# TriMod_Adapter_2.net
KiCad netlist of a schematic drawn in Altium Designer
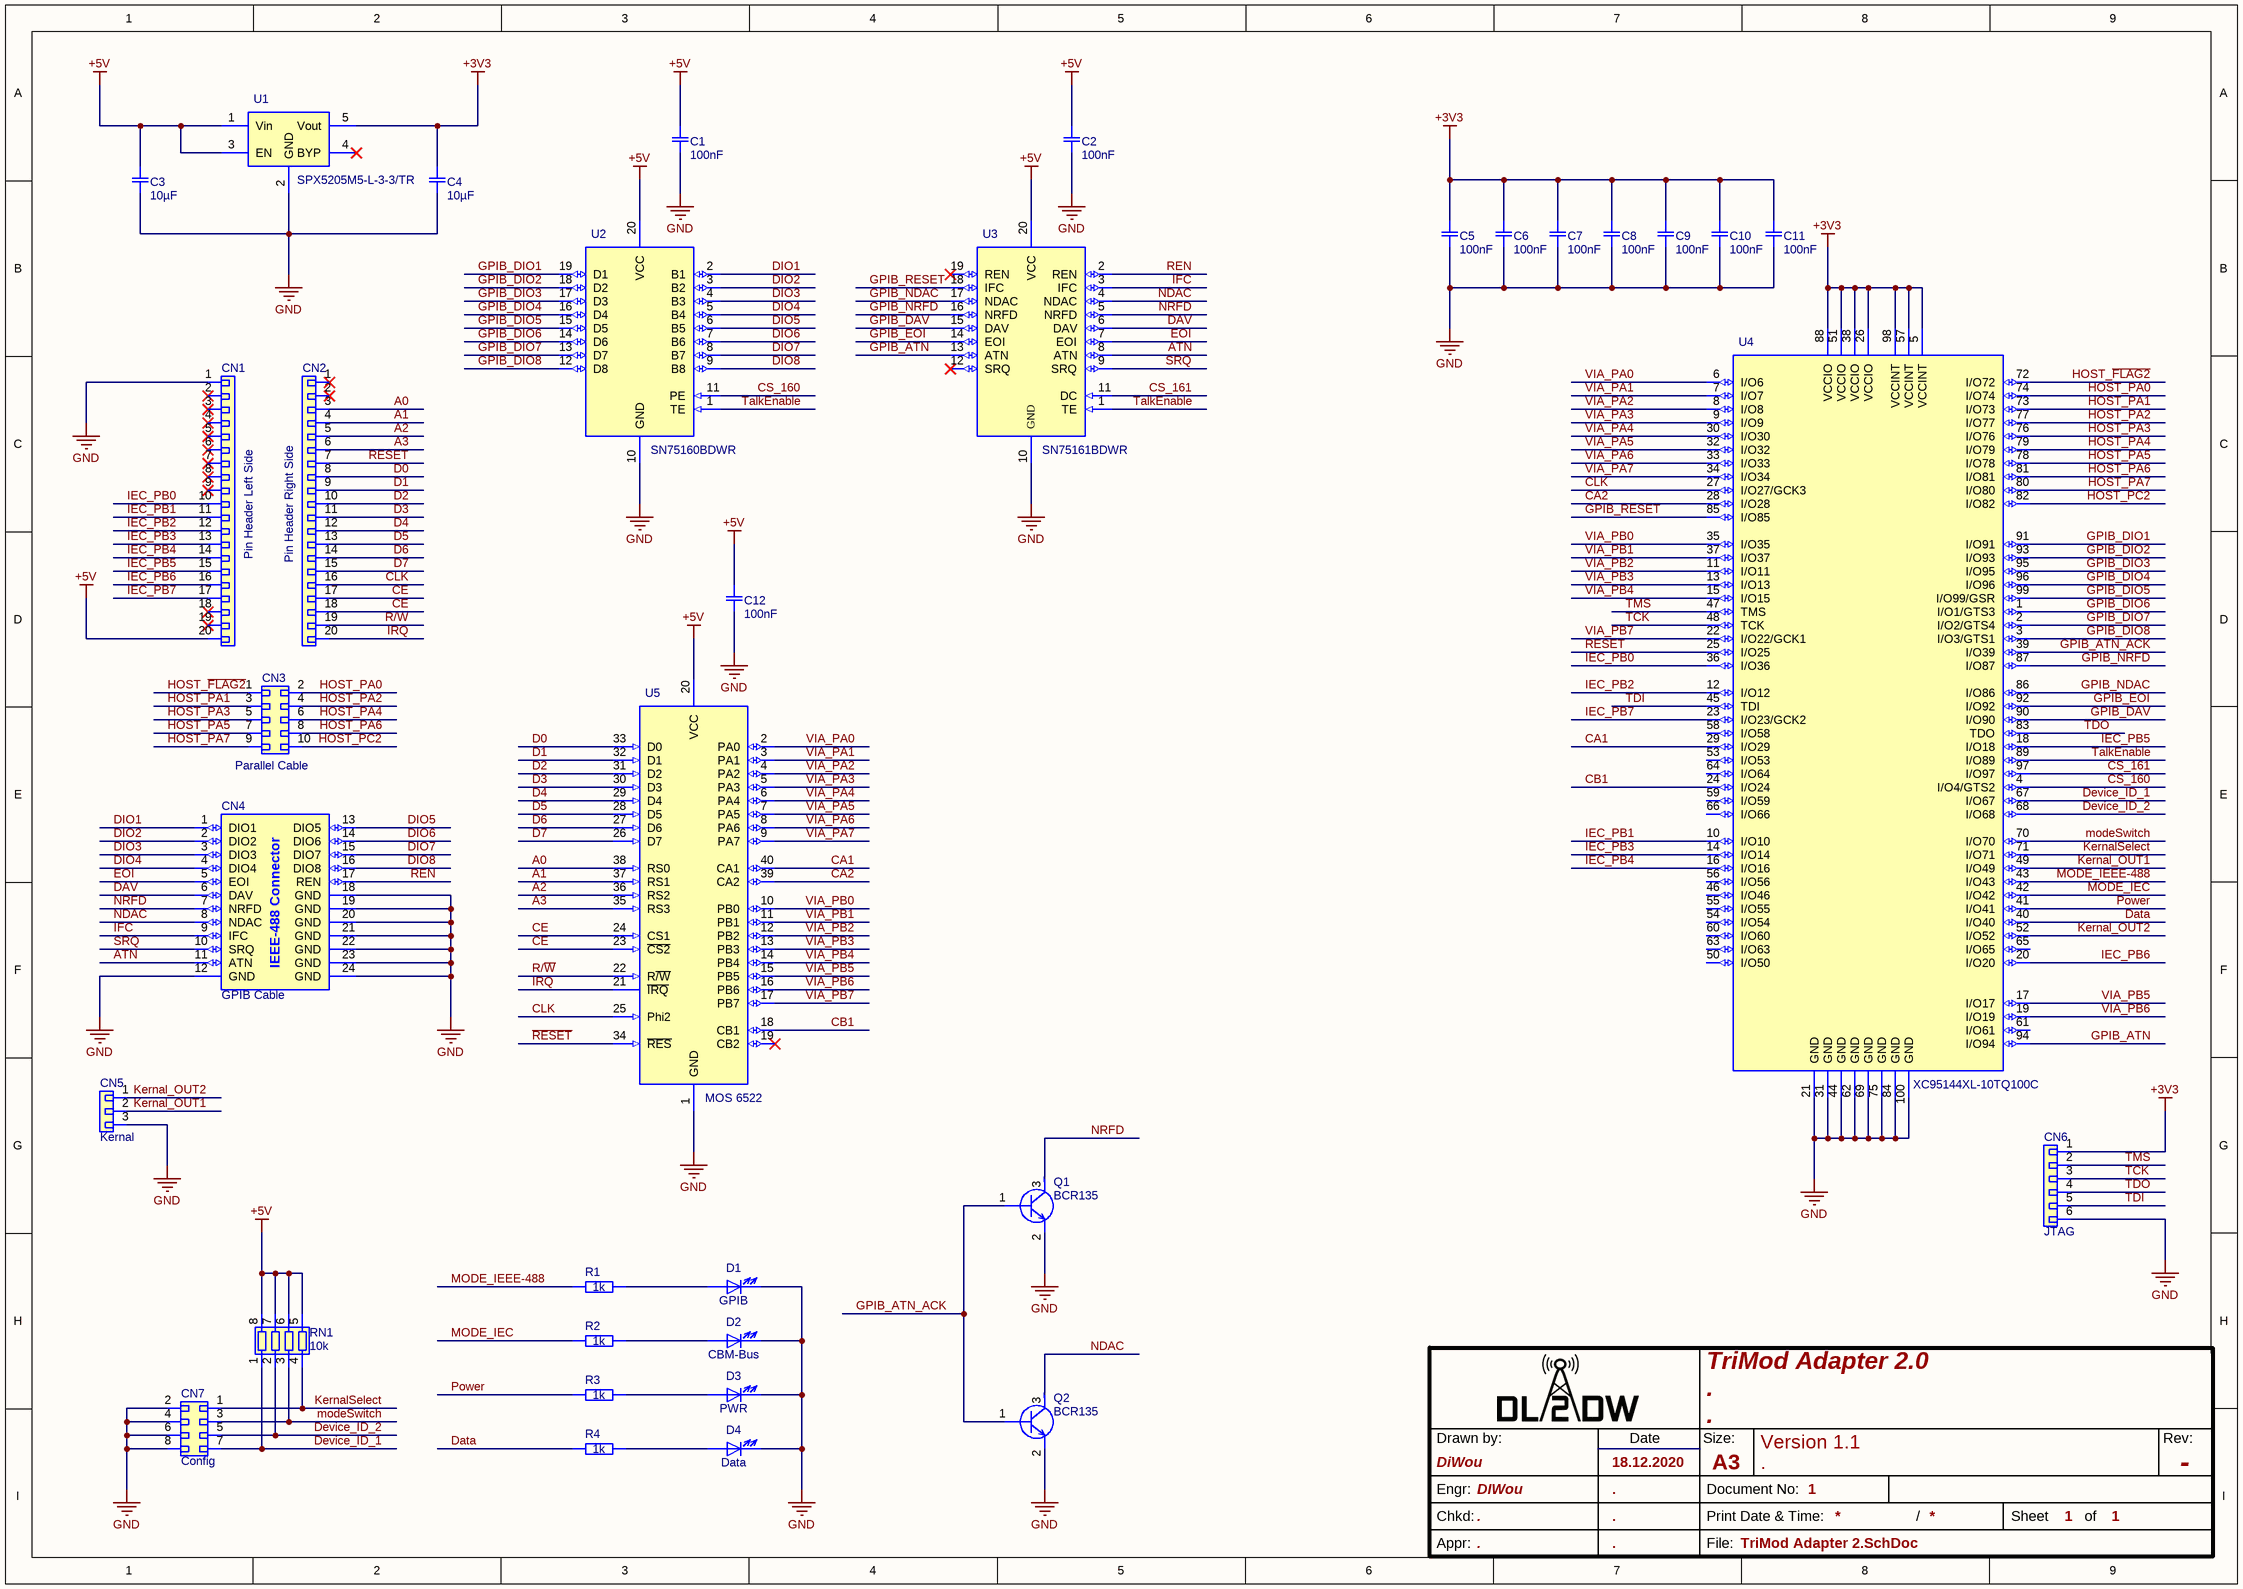
[diagram p0: TriMod Adapter 2.SchDoc]

(export (version "E")
  (design (tool "Eeschema 10.0.6"))
  (components
    (comp (ref "C1")
      (value "100nF")
      (footprint "CAP 100nF SMD 0603 C0603C104J3RACTU")
      (fields (field (name "TOLERANCE") "5%") (field (name "VOLTAGE") "25V"))
      (libsource (lib "PCB-Tech Cloud") (part "Capacitor"))
    )
    (comp (ref "C2")
      (value "100nF")
      (footprint "CAP 100nF SMD 0603 C0603C104J3RACTU")
      (fields (field (name "TOLERANCE") "5%") (field (name "VOLTAGE") "25V"))
      (libsource (lib "PCB-Tech Cloud") (part "Capacitor"))
    )
    (comp (ref "C3")
      (value "10µF")
      (footprint "Kemet C0805CxxxK8RACTU Series H=1.4mm")
      (description "KEMET - C0805C106K8RACTU - CAP, 10µF, 10V, 10%, X7R, 0805")
      (fields (field (name "VOLTAGE") "10V") (field (name "TOLERANCE") "10%"))
      (libsource (lib "PCB-Tech Cloud") (part "Capacitor"))
    )
    (comp (ref "C4")
      (value "10µF")
      (footprint "Kemet C0805CxxxK8RACTU Series H=1.4mm")
      (description "KEMET - C0805C106K8RACTU - CAP, 10µF, 10V, 10%, X7R, 0805")
      (fields (field (name "VOLTAGE") "10V") (field (name "TOLERANCE") "10%"))
      (libsource (lib "PCB-Tech Cloud") (part "Capacitor"))
    )
    (comp (ref "C5")
      (value "100nF")
      (footprint "CAP 100nF SMD 0603 C0603C104J3RACTU")
      (fields (field (name "TOLERANCE") "5%") (field (name "VOLTAGE") "25V"))
      (libsource (lib "PCB-Tech Cloud") (part "Capacitor"))
    )
    (comp (ref "C6")
      (value "100nF")
      (footprint "CAP 100nF SMD 0603 C0603C104J3RACTU")
      (fields (field (name "TOLERANCE") "5%") (field (name "VOLTAGE") "25V"))
      (libsource (lib "PCB-Tech Cloud") (part "Capacitor"))
    )
    (comp (ref "C7")
      (value "100nF")
      (footprint "CAP 100nF SMD 0603 C0603C104J3RACTU")
      (fields (field (name "TOLERANCE") "5%") (field (name "VOLTAGE") "25V"))
      (libsource (lib "PCB-Tech Cloud") (part "Capacitor"))
    )
    (comp (ref "C8")
      (value "100nF")
      (footprint "CAP 100nF SMD 0603 C0603C104J3RACTU")
      (fields (field (name "TOLERANCE") "5%") (field (name "VOLTAGE") "25V"))
      (libsource (lib "PCB-Tech Cloud") (part "Capacitor"))
    )
    (comp (ref "C9")
      (value "100nF")
      (footprint "CAP 100nF SMD 0603 C0603C104J3RACTU")
      (fields (field (name "TOLERANCE") "5%") (field (name "VOLTAGE") "25V"))
      (libsource (lib "PCB-Tech Cloud") (part "Capacitor"))
    )
    (comp (ref "C10")
      (value "100nF")
      (footprint "CAP 100nF SMD 0603 C0603C104J3RACTU")
      (fields (field (name "TOLERANCE") "5%") (field (name "VOLTAGE") "25V"))
      (libsource (lib "PCB-Tech Cloud") (part "Capacitor"))
    )
    (comp (ref "C11")
      (value "100nF")
      (footprint "CAP 100nF SMD 0603 C0603C104J3RACTU")
      (fields (field (name "TOLERANCE") "5%") (field (name "VOLTAGE") "25V"))
      (libsource (lib "PCB-Tech Cloud") (part "Capacitor"))
    )
    (comp (ref "C12")
      (value "100nF")
      (footprint "CAP 100nF SMD 0603 C0603C104J3RACTU")
      (fields (field (name "TOLERANCE") "5%") (field (name "VOLTAGE") "25V"))
      (libsource (lib "PCB-Tech Cloud") (part "Capacitor"))
    )
    (comp (ref "CN1")
      (value "Pin Header Left Side")
      (footprint "Pin Header 01x20 2.54mm precision Horizontal Male")
      (description "Conn Header Vert 20POS 2MM")
      (libsource (lib "") (part "CONN 01x20_1"))
    )
    (comp (ref "CN2")
      (value "Pin Header Right Side")
      (footprint "Pin Header 01x20 2.54mm precision Horizontal Male")
      (description "Conn Header Vert 20POS 2MM")
      (libsource (lib "PCB-Tech Cloud") (part "CONN 01x20"))
    )
    (comp (ref "CN3")
      (value "Parallel Cable")
      (footprint "MPE 369-1-010 Buchsenleisten MicroMatch 1,27 mm,2X05,gerade")
      (description "Grid pitch: 1.27 mm BL2/15-0400GTT-010 RU MPE Garry Conten")
      (libsource (lib "PCB-Tech Cloud") (part "CONN 02x05 Odd Even mirrored"))
    )
    (comp (ref "CN4")
      (value "GPIB Cable")
      (footprint "IEEE-488 Micro Match Connector")
      (description "IEEE-488 IDC Connector Right Angle or Straight")
      (libsource (lib "PCB-Tech Cloud") (part "IEEE-488 Connector"))
    )
    (comp (ref "CN5")
      (value "Kernal")
      (footprint "Pin Header 01x03 2.54mm Horizontal Male")
      (description "CONN HEADER .100\" SNGL STR 3POS")
      (libsource (lib "PCB-Tech Cloud") (part "CONN 01x03"))
    )
    (comp (ref "CN6")
      (value "JTAG")
      (footprint "Pin Header 01x06 2.54mm Horizontal Male")
      (description "CONN HEADER VERT 6POS 2.54MM")
      (libsource (lib "PCB-Tech Cloud") (part "CONN 01x06"))
    )
    (comp (ref "CN7")
      (value "Config")
      (footprint "Pin Header 02x04 2.54mm Horizontal Male")
      (description "CONN HEADER .100\" DUAL STR 8POS")
      (libsource (lib "PCB-Tech Cloud") (part "CONN 02x04 Odd Even"))
    )
    (comp (ref "D1")
      (value "GPIB")
      (footprint "LED Blue SMD 0603")
      (description "LED BLUE DIFFUSED 0603 SMD")
      (libsource (lib "PCB-Tech Cloud") (part "LED Standard"))
    )
    (comp (ref "D2")
      (value "CBM-Bus")
      (footprint "LED Green SMD 0603")
      (description "LED BLUE DIFFUSED 0603 SMD")
      (libsource (lib "PCB-Tech Cloud") (part "LED Standard"))
    )
    (comp (ref "D3")
      (value "PWR")
      (footprint "LED Red SMD 0603")
      (description "LED RED DIFFUSED 0603 SMD")
      (libsource (lib "PCB-Tech Cloud") (part "LED Standard"))
    )
    (comp (ref "D4")
      (value "Data")
      (footprint "LED Yellow SMD 0603")
      (description "LED YELLOW DIFFUSED 0603 SMD")
      (libsource (lib "PCB-Tech Cloud") (part "LED Standard"))
    )
    (comp (ref "Q1")
      (value "BCR135")
      (footprint "BCR135 SOT23")
      (description "BCR135 Series NPN 50 V 100 mA SMT Silicon Digital Transistor - SOT-23-3")
      (libsource (lib "PCB-Tech Cloud") (part "Transistor NPN BEC"))
    )
    (comp (ref "Q2")
      (value "BCR135")
      (footprint "BCR135 SOT23")
      (description "BCR135 Series NPN 50 V 100 mA SMT Silicon Digital Transistor - SOT-23-3")
      (libsource (lib "PCB-Tech Cloud") (part "Transistor NPN BEC"))
    )
    (comp (ref "R1")
      (value "1k")
      (footprint "1k Ohm R 0603 SMD")
      (description "RES SMD 1K OHM 1% 1/10W 0603")
      (fields (field (name "TOLERANCE") "1%"))
      (libsource (lib "PCB-Tech Cloud") (part "Resistor"))
    )
    (comp (ref "R2")
      (value "1k")
      (footprint "1k Ohm R 0603 SMD")
      (description "RES SMD 1K OHM 1% 1/10W 0603")
      (fields (field (name "TOLERANCE") "1%"))
      (libsource (lib "PCB-Tech Cloud") (part "Resistor"))
    )
    (comp (ref "R3")
      (value "1k")
      (footprint "1k Ohm R 0603 SMD")
      (description "RES SMD 1K OHM 1% 1/10W 0603")
      (fields (field (name "TOLERANCE") "1%"))
      (libsource (lib "PCB-Tech Cloud") (part "Resistor"))
    )
    (comp (ref "R4")
      (value "1k")
      (footprint "1k Ohm R 0603 SMD")
      (description "RES SMD 1K OHM 1% 1/10W 0603")
      (fields (field (name "TOLERANCE") "1%"))
      (libsource (lib "PCB-Tech Cloud") (part "Resistor"))
    )
    (comp (ref "RN1")
      (value "10k")
      (footprint "RES ARRAY 4 RES 10K OHM 0804")
      (description "RES ARRAY 4 RES 10K OHM 0804")
      (fields (field (name "TOLERANCE") "1%"))
      (libsource (lib "PCB-Tech Cloud") (part "Resistor Pack x4"))
    )
    (comp (ref "U1")
      (value "SPX5205M5-L-3-3/TR")
      (footprint "SOT-23-5")
      (description "LDO Regulator Pos 3.3V 0.15A 5-Pin SOT-23 T/R")
      (libsource (lib "PCB-Tech Cloud") (part "SPX5205M5-L-3-3/TR"))
    )
    (comp (ref "U2")
      (value "SN75160BDWR")
      (footprint "SN75160BDWR SOIC-20 W7.5mm P1,27mm")
      (description "TEXAS INSTRUMENTS         SN75160BDWR.            GENERAL-PURPOSE INTERFACE BUS  ((NW))")
      (libsource (lib "PCB-Tech Cloud") (part "SN75160B"))
    )
    (comp (ref "U3")
      (value "SN75161BDWR")
      (footprint "SN75161BDWR SOIC-20 W7.5mm P1,27mm")
      (description "TEXAS INSTRUMENTS         SN75161BDWR")
      (libsource (lib "PCB-Tech Cloud") (part "SN75161B"))
    )
    (comp (ref "U4")
      (value "XC95144XL-10TQ100C")
      (footprint "TQFP-100 P0.5mm XC95144XL-7TQ100C")
      (description "IC CPLD 144MC 7.5NS 100TQFP")
      (libsource (lib "PCB-Tech Cloud") (part "XC95144XL-TQG100C"))
    )
    (comp (ref "U5")
      (value "MOS 6522")
      (footprint "MOS 6522 with Socket")
      (description "I/O Controller Interface IC Versatile Interface Adapter")
      (libsource (lib "PCB-Tech Cloud") (part "MOS 6522"))
    )
  )
  (nets
    (net (code "1") (name "+3V3") (class "Default")
      (node (ref "C10") (pin "2") (pinfunction "2_2") (pintype "passive"))
      (node (ref "C11") (pin "2") (pinfunction "2_2") (pintype "passive"))
      (node (ref "C4") (pin "2") (pinfunction "2_2") (pintype "passive"))
      (node (ref "C5") (pin "2") (pinfunction "2_2") (pintype "passive"))
      (node (ref "C6") (pin "2") (pinfunction "2_2") (pintype "passive"))
      (node (ref "C7") (pin "2") (pinfunction "2_2") (pintype "passive"))
      (node (ref "C8") (pin "2") (pinfunction "2_2") (pintype "passive"))
      (node (ref "C9") (pin "2") (pinfunction "2_2") (pintype "passive"))
      (node (ref "CN6") (pin "1") (pinfunction "1_1") (pintype "passive"))
      (node (ref "U1") (pin "5") (pinfunction "Vout_5") (pintype "power_in"))
      (node (ref "U4") (pin "26") (pinfunction "VCCIO_26") (pintype "power_in"))
      (node (ref "U4") (pin "38") (pinfunction "VCCIO_38") (pintype "power_in"))
      (node (ref "U4") (pin "5") (pinfunction "VCCINT_5") (pintype "power_in"))
      (node (ref "U4") (pin "51") (pinfunction "VCCIO_51") (pintype "power_in"))
      (node (ref "U4") (pin "57") (pinfunction "VCCINT_57") (pintype "power_in"))
      (node (ref "U4") (pin "88") (pinfunction "VCCIO_88") (pintype "power_in"))
      (node (ref "U4") (pin "98") (pinfunction "VCCINT_98") (pintype "power_in"))
    )
    (net (code "2") (name "+5V") (class "Default")
      (node (ref "C1") (pin "2") (pinfunction "2_2") (pintype "passive"))
      (node (ref "C12") (pin "2") (pinfunction "2_2") (pintype "passive"))
      (node (ref "C2") (pin "2") (pinfunction "2_2") (pintype "passive"))
      (node (ref "C3") (pin "2") (pinfunction "2_2") (pintype "passive"))
      (node (ref "CN1") (pin "20") (pinfunction "20_20") (pintype "passive"))
      (node (ref "RN1") (pin "5") (pinfunction "5_5") (pintype "passive"))
      (node (ref "RN1") (pin "6") (pinfunction "6_6") (pintype "passive"))
      (node (ref "RN1") (pin "7") (pinfunction "7_7") (pintype "passive"))
      (node (ref "RN1") (pin "8") (pinfunction "8_8") (pintype "passive"))
      (node (ref "U1") (pin "1") (pinfunction "Vin_1") (pintype "power_in"))
      (node (ref "U1") (pin "3") (pinfunction "EN_3") (pintype "passive"))
      (node (ref "U2") (pin "20") (pinfunction "VCC_20") (pintype "power_in"))
      (node (ref "U3") (pin "20") (pinfunction "VCC_20") (pintype "power_in"))
      (node (ref "U5") (pin "20") (pinfunction "VCC_20") (pintype "power_in"))
    )
    (net (code "3") (name "/A0") (class "Default")
      (node (ref "CN2") (pin "3") (pinfunction "3_3") (pintype "passive"))
      (node (ref "U5") (pin "38") (pinfunction "RS0_38") (pintype "input"))
    )
    (net (code "4") (name "/A1") (class "Default")
      (node (ref "CN2") (pin "4") (pinfunction "4_4") (pintype "passive"))
      (node (ref "U5") (pin "37") (pinfunction "RS1_37") (pintype "input"))
    )
    (net (code "5") (name "/A2") (class "Default")
      (node (ref "CN2") (pin "5") (pinfunction "5_5") (pintype "passive"))
      (node (ref "U5") (pin "36") (pinfunction "RS2_36") (pintype "input"))
    )
    (net (code "6") (name "/A3") (class "Default")
      (node (ref "CN2") (pin "6") (pinfunction "6_6") (pintype "passive"))
      (node (ref "U5") (pin "35") (pinfunction "RS3_35") (pintype "input"))
    )
    (net (code "7") (name "/ATN") (class "Default")
      (node (ref "CN4") (pin "11") (pinfunction "ATN_11") (pintype "bidirectional"))
      (node (ref "U3") (pin "8") (pinfunction "ATN_8") (pintype "bidirectional"))
    )
    (net (code "8") (name "/CA1") (class "Default")
      (node (ref "U4") (pin "29") (pinfunction "I/O29_29") (pintype "bidirectional"))
      (node (ref "U5") (pin "40") (pinfunction "CA1_40") (pintype "bidirectional"))
    )
    (net (code "9") (name "/CA2") (class "Default")
      (node (ref "U4") (pin "28") (pinfunction "I/O28_28") (pintype "bidirectional"))
      (node (ref "U5") (pin "39") (pinfunction "CA2_39") (pintype "bidirectional"))
    )
    (net (code "10") (name "/CB1") (class "Default")
      (node (ref "U4") (pin "24") (pinfunction "I/O24_24") (pintype "bidirectional"))
      (node (ref "U5") (pin "18") (pinfunction "CB1_18") (pintype "bidirectional"))
    )
    (net (code "11") (name "/CE") (class "Default")
      (node (ref "CN2") (pin "17") (pinfunction "17_17") (pintype "passive"))
      (node (ref "U5") (pin "24") (pinfunction "CS1_24") (pintype "input"))
    )
    (net (code "12") (name "/CLK") (class "Default")
      (node (ref "CN2") (pin "16") (pinfunction "16_16") (pintype "passive"))
      (node (ref "U4") (pin "27") (pinfunction "I/O27/GCK3_27") (pintype "bidirectional"))
      (node (ref "U5") (pin "25") (pinfunction "Phi2_25") (pintype "input"))
    )
    (net (code "13") (name "/CS_160") (class "Default")
      (node (ref "U2") (pin "11") (pinfunction "PE_11") (pintype "input"))
      (node (ref "U4") (pin "4") (pinfunction "I/O4/GTS2_4") (pintype "bidirectional"))
    )
    (net (code "14") (name "/CS_161") (class "Default")
      (node (ref "U3") (pin "11") (pinfunction "DC_11") (pintype "input"))
      (node (ref "U4") (pin "97") (pinfunction "I/O97_97") (pintype "bidirectional"))
    )
    (net (code "15") (name "/D0") (class "Default")
      (node (ref "CN2") (pin "8") (pinfunction "8_8") (pintype "passive"))
      (node (ref "U5") (pin "33") (pinfunction "D0_33") (pintype "input"))
    )
    (net (code "16") (name "/D1") (class "Default")
      (node (ref "CN2") (pin "9") (pinfunction "9_9") (pintype "passive"))
      (node (ref "U5") (pin "32") (pinfunction "D1_32") (pintype "input"))
    )
    (net (code "17") (name "/D2") (class "Default")
      (node (ref "CN2") (pin "10") (pinfunction "10_10") (pintype "passive"))
      (node (ref "U5") (pin "31") (pinfunction "D2_31") (pintype "input"))
    )
    (net (code "18") (name "/D3") (class "Default")
      (node (ref "CN2") (pin "11") (pinfunction "11_11") (pintype "passive"))
      (node (ref "U5") (pin "30") (pinfunction "D3_30") (pintype "input"))
    )
    (net (code "19") (name "/D4") (class "Default")
      (node (ref "CN2") (pin "12") (pinfunction "12_12") (pintype "passive"))
      (node (ref "U5") (pin "29") (pinfunction "D4_29") (pintype "input"))
    )
    (net (code "20") (name "/D5") (class "Default")
      (node (ref "CN2") (pin "13") (pinfunction "13_13") (pintype "passive"))
      (node (ref "U5") (pin "28") (pinfunction "D5_28") (pintype "input"))
    )
    (net (code "21") (name "/D6") (class "Default")
      (node (ref "CN2") (pin "14") (pinfunction "14_14") (pintype "passive"))
      (node (ref "U5") (pin "27") (pinfunction "D6_27") (pintype "input"))
    )
    (net (code "22") (name "/D7") (class "Default")
      (node (ref "CN2") (pin "15") (pinfunction "15_15") (pintype "passive"))
      (node (ref "U5") (pin "26") (pinfunction "D7_26") (pintype "input"))
    )
    (net (code "23") (name "/DAV") (class "Default")
      (node (ref "CN4") (pin "6") (pinfunction "DAV_6") (pintype "bidirectional"))
      (node (ref "U3") (pin "6") (pinfunction "DAV_6") (pintype "bidirectional"))
    )
    (net (code "24") (name "/DIO1") (class "Default")
      (node (ref "CN4") (pin "1") (pinfunction "DIO1_1") (pintype "bidirectional"))
      (node (ref "U2") (pin "2") (pinfunction "B1_2") (pintype "bidirectional"))
    )
    (net (code "25") (name "/DIO2") (class "Default")
      (node (ref "CN4") (pin "2") (pinfunction "DIO2_2") (pintype "bidirectional"))
      (node (ref "U2") (pin "3") (pinfunction "B2_3") (pintype "bidirectional"))
    )
    (net (code "26") (name "/DIO3") (class "Default")
      (node (ref "CN4") (pin "3") (pinfunction "DIO3_3") (pintype "bidirectional"))
      (node (ref "U2") (pin "4") (pinfunction "B3_4") (pintype "bidirectional"))
    )
    (net (code "27") (name "/DIO4") (class "Default")
      (node (ref "CN4") (pin "4") (pinfunction "DIO4_4") (pintype "bidirectional"))
      (node (ref "U2") (pin "5") (pinfunction "B4_5") (pintype "bidirectional"))
    )
    (net (code "28") (name "/DIO5") (class "Default")
      (node (ref "CN4") (pin "13") (pinfunction "DIO5_13") (pintype "bidirectional"))
      (node (ref "U2") (pin "6") (pinfunction "B5_6") (pintype "bidirectional"))
    )
    (net (code "29") (name "/DIO6") (class "Default")
      (node (ref "CN4") (pin "14") (pinfunction "DIO6_14") (pintype "bidirectional"))
      (node (ref "U2") (pin "7") (pinfunction "B6_7") (pintype "bidirectional"))
    )
    (net (code "30") (name "/DIO7") (class "Default")
      (node (ref "CN4") (pin "15") (pinfunction "DIO7_15") (pintype "bidirectional"))
      (node (ref "U2") (pin "8") (pinfunction "B7_8") (pintype "bidirectional"))
    )
    (net (code "31") (name "/DIO8") (class "Default")
      (node (ref "CN4") (pin "16") (pinfunction "DIO8_16") (pintype "bidirectional"))
      (node (ref "U2") (pin "9") (pinfunction "B8_9") (pintype "bidirectional"))
    )
    (net (code "32") (name "/Data") (class "Default")
      (node (ref "R4") (pin "1") (pinfunction "1_1") (pintype "passive"))
      (node (ref "U4") (pin "40") (pinfunction "I/O40_40") (pintype "bidirectional"))
    )
    (net (code "33") (name "/Device_ID_1") (class "Default")
      (node (ref "CN7") (pin "7") (pinfunction "7_7") (pintype "passive"))
      (node (ref "RN1") (pin "1") (pinfunction "1_1") (pintype "passive"))
      (node (ref "U4") (pin "67") (pinfunction "I/O67_67") (pintype "bidirectional"))
    )
    (net (code "34") (name "/Device_ID_2") (class "Default")
      (node (ref "CN7") (pin "5") (pinfunction "5_5") (pintype "passive"))
      (node (ref "RN1") (pin "2") (pinfunction "2_2") (pintype "passive"))
      (node (ref "U4") (pin "68") (pinfunction "I/O68_68") (pintype "bidirectional"))
    )
    (net (code "35") (name "/EOI") (class "Default")
      (node (ref "CN4") (pin "5") (pinfunction "EOI_5") (pintype "bidirectional"))
      (node (ref "U3") (pin "7") (pinfunction "EOI_7") (pintype "bidirectional"))
    )
    (net (code "36") (name "/GPIB_ATN") (class "Default")
      (node (ref "U3") (pin "13") (pinfunction "ATN_13") (pintype "bidirectional"))
      (node (ref "U4") (pin "94") (pinfunction "I/O94_94") (pintype "bidirectional"))
    )
    (net (code "37") (name "/GPIB_ATN_ACK") (class "Default")
      (node (ref "Q1") (pin "1") (pinfunction "1_1") (pintype "passive"))
      (node (ref "Q2") (pin "1") (pinfunction "1_1") (pintype "passive"))
      (node (ref "U4") (pin "39") (pinfunction "I/O39_39") (pintype "bidirectional"))
    )
    (net (code "38") (name "/GPIB_DAV") (class "Default")
      (node (ref "U3") (pin "15") (pinfunction "DAV_15") (pintype "bidirectional"))
      (node (ref "U4") (pin "90") (pinfunction "I/O90_90") (pintype "bidirectional"))
    )
    (net (code "39") (name "/GPIB_DIO1") (class "Default")
      (node (ref "U2") (pin "19") (pinfunction "D1_19") (pintype "bidirectional"))
      (node (ref "U4") (pin "91") (pinfunction "I/O91_91") (pintype "bidirectional"))
    )
    (net (code "40") (name "/GPIB_DIO2") (class "Default")
      (node (ref "U2") (pin "18") (pinfunction "D2_18") (pintype "bidirectional"))
      (node (ref "U4") (pin "93") (pinfunction "I/O93_93") (pintype "bidirectional"))
    )
    (net (code "41") (name "/GPIB_DIO3") (class "Default")
      (node (ref "U2") (pin "17") (pinfunction "D3_17") (pintype "bidirectional"))
      (node (ref "U4") (pin "95") (pinfunction "I/O95_95") (pintype "bidirectional"))
    )
    (net (code "42") (name "/GPIB_DIO4") (class "Default")
      (node (ref "U2") (pin "16") (pinfunction "D4_16") (pintype "bidirectional"))
      (node (ref "U4") (pin "96") (pinfunction "I/O96_96") (pintype "bidirectional"))
    )
    (net (code "43") (name "/GPIB_DIO5") (class "Default")
      (node (ref "U2") (pin "15") (pinfunction "D5_15") (pintype "bidirectional"))
      (node (ref "U4") (pin "99") (pinfunction "I/O99/GSR_99") (pintype "bidirectional"))
    )
    (net (code "44") (name "/GPIB_DIO6") (class "Default")
      (node (ref "U2") (pin "14") (pinfunction "D6_14") (pintype "bidirectional"))
      (node (ref "U4") (pin "1") (pinfunction "I/O1/GTS3_1") (pintype "bidirectional"))
    )
    (net (code "45") (name "/GPIB_DIO7") (class "Default")
      (node (ref "U2") (pin "13") (pinfunction "D7_13") (pintype "bidirectional"))
      (node (ref "U4") (pin "2") (pinfunction "I/O2/GTS4_2") (pintype "bidirectional"))
    )
    (net (code "46") (name "/GPIB_DIO8") (class "Default")
      (node (ref "U2") (pin "12") (pinfunction "D8_12") (pintype "bidirectional"))
      (node (ref "U4") (pin "3") (pinfunction "I/O3/GTS1_3") (pintype "bidirectional"))
    )
    (net (code "47") (name "/GPIB_EOI") (class "Default")
      (node (ref "U3") (pin "14") (pinfunction "EOI_14") (pintype "bidirectional"))
      (node (ref "U4") (pin "92") (pinfunction "I/O92_92") (pintype "bidirectional"))
    )
    (net (code "48") (name "/GPIB_NDAC") (class "Default")
      (node (ref "U3") (pin "17") (pinfunction "NDAC_17") (pintype "bidirectional"))
      (node (ref "U4") (pin "86") (pinfunction "I/O86_86") (pintype "bidirectional"))
    )
    (net (code "49") (name "/GPIB_NRFD") (class "Default")
      (node (ref "U3") (pin "16") (pinfunction "NRFD_16") (pintype "bidirectional"))
      (node (ref "U4") (pin "87") (pinfunction "I/O87_87") (pintype "bidirectional"))
    )
    (net (code "50") (name "/GPIB_RESET") (class "Default")
      (node (ref "U3") (pin "18") (pinfunction "IFC_18") (pintype "bidirectional"))
      (node (ref "U4") (pin "85") (pinfunction "I/O85_85") (pintype "bidirectional"))
    )
    (net (code "51") (name "/HOST_PA0") (class "Default")
      (node (ref "CN3") (pin "2") (pinfunction "2_2") (pintype "passive"))
      (node (ref "U4") (pin "74") (pinfunction "I/O74_74") (pintype "bidirectional"))
    )
    (net (code "52") (name "/HOST_PA1") (class "Default")
      (node (ref "CN3") (pin "3") (pinfunction "3_3") (pintype "passive"))
      (node (ref "U4") (pin "73") (pinfunction "I/O73_73") (pintype "bidirectional"))
    )
    (net (code "53") (name "/HOST_PA2") (class "Default")
      (node (ref "CN3") (pin "4") (pinfunction "4_4") (pintype "passive"))
      (node (ref "U4") (pin "77") (pinfunction "I/O77_77") (pintype "bidirectional"))
    )
    (net (code "54") (name "/HOST_PA3") (class "Default")
      (node (ref "CN3") (pin "5") (pinfunction "5_5") (pintype "passive"))
      (node (ref "U4") (pin "76") (pinfunction "I/O76_76") (pintype "bidirectional"))
    )
    (net (code "55") (name "/HOST_PA4") (class "Default")
      (node (ref "CN3") (pin "6") (pinfunction "6_6") (pintype "passive"))
      (node (ref "U4") (pin "79") (pinfunction "I/O79_79") (pintype "bidirectional"))
    )
    (net (code "56") (name "/HOST_PA5") (class "Default")
      (node (ref "CN3") (pin "7") (pinfunction "7_7") (pintype "passive"))
      (node (ref "U4") (pin "78") (pinfunction "I/O78_78") (pintype "bidirectional"))
    )
    (net (code "57") (name "/HOST_PA6") (class "Default")
      (node (ref "CN3") (pin "8") (pinfunction "8_8") (pintype "passive"))
      (node (ref "U4") (pin "81") (pinfunction "I/O81_81") (pintype "bidirectional"))
    )
    (net (code "58") (name "/HOST_PA7") (class "Default")
      (node (ref "CN3") (pin "9") (pinfunction "9_9") (pintype "passive"))
      (node (ref "U4") (pin "80") (pinfunction "I/O80_80") (pintype "bidirectional"))
    )
    (net (code "59") (name "/HOST_~{FLAG2}") (class "Default")
      (node (ref "CN3") (pin "1") (pinfunction "1_1") (pintype "passive"))
      (node (ref "U4") (pin "72") (pinfunction "I/O72_72") (pintype "bidirectional"))
    )
    (net (code "60") (name "/HOST_~{PC2}") (class "Default")
      (node (ref "CN3") (pin "10") (pinfunction "10_10") (pintype "passive"))
      (node (ref "U4") (pin "82") (pinfunction "I/O82_82") (pintype "bidirectional"))
    )
    (net (code "61") (name "/IEC_PB0") (class "Default")
      (node (ref "CN1") (pin "10") (pinfunction "10_10") (pintype "passive"))
      (node (ref "U4") (pin "36") (pinfunction "I/O36_36") (pintype "bidirectional"))
    )
    (net (code "62") (name "/IEC_PB1") (class "Default")
      (node (ref "CN1") (pin "11") (pinfunction "11_11") (pintype "passive"))
      (node (ref "U4") (pin "10") (pinfunction "I/O10_10") (pintype "bidirectional"))
    )
    (net (code "63") (name "/IEC_PB2") (class "Default")
      (node (ref "CN1") (pin "12") (pinfunction "12_12") (pintype "passive"))
      (node (ref "U4") (pin "12") (pinfunction "I/O12_12") (pintype "bidirectional"))
    )
    (net (code "64") (name "/IEC_PB3") (class "Default")
      (node (ref "CN1") (pin "13") (pinfunction "13_13") (pintype "passive"))
      (node (ref "U4") (pin "14") (pinfunction "I/O14_14") (pintype "bidirectional"))
    )
    (net (code "65") (name "/IEC_PB4") (class "Default")
      (node (ref "CN1") (pin "14") (pinfunction "14_14") (pintype "passive"))
      (node (ref "U4") (pin "16") (pinfunction "I/O16_16") (pintype "bidirectional"))
    )
    (net (code "66") (name "/IEC_PB5") (class "Default")
      (node (ref "CN1") (pin "15") (pinfunction "15_15") (pintype "passive"))
      (node (ref "U4") (pin "18") (pinfunction "I/O18_18") (pintype "bidirectional"))
    )
    (net (code "67") (name "/IEC_PB6") (class "Default")
      (node (ref "CN1") (pin "16") (pinfunction "16_16") (pintype "passive"))
      (node (ref "U4") (pin "20") (pinfunction "I/O20_20") (pintype "bidirectional"))
    )
    (net (code "68") (name "/IEC_PB7") (class "Default")
      (node (ref "CN1") (pin "17") (pinfunction "17_17") (pintype "passive"))
      (node (ref "U4") (pin "23") (pinfunction "I/O23/GCK2_23") (pintype "bidirectional"))
    )
    (net (code "69") (name "/IFC") (class "Default")
      (node (ref "CN4") (pin "9") (pinfunction "IFC_9") (pintype "bidirectional"))
      (node (ref "U3") (pin "3") (pinfunction "IFC_3") (pintype "bidirectional"))
    )
    (net (code "70") (name "/KernalSelect") (class "Default")
      (node (ref "CN7") (pin "1") (pinfunction "1_1") (pintype "passive"))
      (node (ref "RN1") (pin "4") (pinfunction "4_4") (pintype "passive"))
      (node (ref "U4") (pin "71") (pinfunction "I/O71_71") (pintype "bidirectional"))
    )
    (net (code "71") (name "/Kernal_OUT1") (class "Default")
      (node (ref "CN5") (pin "2") (pinfunction "2_2") (pintype "passive"))
      (node (ref "U4") (pin "49") (pinfunction "I/O49_49") (pintype "bidirectional"))
    )
    (net (code "72") (name "/Kernal_OUT2") (class "Default")
      (node (ref "CN5") (pin "1") (pinfunction "1_1") (pintype "passive"))
      (node (ref "U4") (pin "52") (pinfunction "I/O52_52") (pintype "bidirectional"))
    )
    (net (code "73") (name "/MODE_IEC") (class "Default")
      (node (ref "R2") (pin "1") (pinfunction "1_1") (pintype "passive"))
      (node (ref "U4") (pin "42") (pinfunction "I/O42_42") (pintype "bidirectional"))
    )
    (net (code "74") (name "/MODE_IEEE-488") (class "Default")
      (node (ref "R1") (pin "1") (pinfunction "1_1") (pintype "passive"))
      (node (ref "U4") (pin "43") (pinfunction "I/O43_43") (pintype "bidirectional"))
    )
    (net (code "75") (name "/NDAC") (class "Default")
      (node (ref "CN4") (pin "8") (pinfunction "NDAC_8") (pintype "bidirectional"))
      (node (ref "Q2") (pin "3") (pinfunction "3_3") (pintype "passive"))
      (node (ref "U3") (pin "4") (pinfunction "NDAC_4") (pintype "bidirectional"))
    )
    (net (code "76") (name "/NRFD") (class "Default")
      (node (ref "CN4") (pin "7") (pinfunction "NRFD_7") (pintype "bidirectional"))
      (node (ref "Q1") (pin "3") (pinfunction "3_3") (pintype "passive"))
      (node (ref "U3") (pin "5") (pinfunction "NRFD_5") (pintype "bidirectional"))
    )
    (net (code "77") (name "/Power") (class "Default")
      (node (ref "R3") (pin "1") (pinfunction "1_1") (pintype "passive"))
      (node (ref "U4") (pin "41") (pinfunction "I/O41_41") (pintype "bidirectional"))
    )
    (net (code "78") (name "/REN") (class "Default")
      (node (ref "CN4") (pin "17") (pinfunction "REN_17") (pintype "bidirectional"))
      (node (ref "U3") (pin "2") (pinfunction "REN_2") (pintype "bidirectional"))
    )
    (net (code "79") (name "/R{slash}~{W}") (class "Default")
      (node (ref "CN2") (pin "19") (pinfunction "19_19") (pintype "passive"))
      (node (ref "U5") (pin "22") (pinfunction "R~{/W}_22") (pintype "input"))
    )
    (net (code "80") (name "/SRQ") (class "Default")
      (node (ref "CN4") (pin "10") (pinfunction "SRQ_10") (pintype "bidirectional"))
      (node (ref "U3") (pin "9") (pinfunction "SRQ_9") (pintype "bidirectional"))
    )
    (net (code "81") (name "/TCK") (class "Default")
      (node (ref "CN6") (pin "3") (pinfunction "3_3") (pintype "passive"))
      (node (ref "U4") (pin "48") (pinfunction "TCK_48") (pintype "bidirectional"))
    )
    (net (code "82") (name "/TDI") (class "Default")
      (node (ref "CN6") (pin "5") (pinfunction "5_5") (pintype "passive"))
      (node (ref "U4") (pin "45") (pinfunction "TDI_45") (pintype "bidirectional"))
    )
    (net (code "83") (name "/TDO") (class "Default")
      (node (ref "CN6") (pin "4") (pinfunction "4_4") (pintype "passive"))
      (node (ref "U4") (pin "83") (pinfunction "TDO_83") (pintype "bidirectional"))
    )
    (net (code "84") (name "/TMS") (class "Default")
      (node (ref "CN6") (pin "2") (pinfunction "2_2") (pintype "passive"))
      (node (ref "U4") (pin "47") (pinfunction "TMS_47") (pintype "bidirectional"))
    )
    (net (code "85") (name "/TalkEnable") (class "Default")
      (node (ref "U2") (pin "1") (pinfunction "TE_1") (pintype "input"))
      (node (ref "U3") (pin "1") (pinfunction "TE_1") (pintype "input"))
      (node (ref "U4") (pin "89") (pinfunction "I/O89_89") (pintype "bidirectional"))
    )
    (net (code "86") (name "/VIA_PA0") (class "Default")
      (node (ref "U4") (pin "6") (pinfunction "I/O6_6") (pintype "bidirectional"))
      (node (ref "U5") (pin "2") (pinfunction "PA0_2") (pintype "bidirectional"))
    )
    (net (code "87") (name "/VIA_PA1") (class "Default")
      (node (ref "U4") (pin "7") (pinfunction "I/O7_7") (pintype "bidirectional"))
      (node (ref "U5") (pin "3") (pinfunction "PA1_3") (pintype "bidirectional"))
    )
    (net (code "88") (name "/VIA_PA2") (class "Default")
      (node (ref "U4") (pin "8") (pinfunction "I/O8_8") (pintype "bidirectional"))
      (node (ref "U5") (pin "4") (pinfunction "PA2_4") (pintype "bidirectional"))
    )
    (net (code "89") (name "/VIA_PA3") (class "Default")
      (node (ref "U4") (pin "9") (pinfunction "I/O9_9") (pintype "bidirectional"))
      (node (ref "U5") (pin "5") (pinfunction "PA3_5") (pintype "bidirectional"))
    )
    (net (code "90") (name "/VIA_PA4") (class "Default")
      (node (ref "U4") (pin "30") (pinfunction "I/O30_30") (pintype "bidirectional"))
      (node (ref "U5") (pin "6") (pinfunction "PA4_6") (pintype "bidirectional"))
    )
    (net (code "91") (name "/VIA_PA5") (class "Default")
      (node (ref "U4") (pin "32") (pinfunction "I/O32_32") (pintype "bidirectional"))
      (node (ref "U5") (pin "7") (pinfunction "PA5_7") (pintype "bidirectional"))
    )
    (net (code "92") (name "/VIA_PA6") (class "Default")
      (node (ref "U4") (pin "33") (pinfunction "I/O33_33") (pintype "bidirectional"))
      (node (ref "U5") (pin "8") (pinfunction "PA6_8") (pintype "bidirectional"))
    )
    (net (code "93") (name "/VIA_PA7") (class "Default")
      (node (ref "U4") (pin "34") (pinfunction "I/O34_34") (pintype "bidirectional"))
      (node (ref "U5") (pin "9") (pinfunction "PA7_9") (pintype "bidirectional"))
    )
    (net (code "94") (name "/VIA_PB0") (class "Default")
      (node (ref "U4") (pin "35") (pinfunction "I/O35_35") (pintype "bidirectional"))
      (node (ref "U5") (pin "10") (pinfunction "PB0_10") (pintype "bidirectional"))
    )
    (net (code "95") (name "/VIA_PB1") (class "Default")
      (node (ref "U4") (pin "37") (pinfunction "I/O37_37") (pintype "bidirectional"))
      (node (ref "U5") (pin "11") (pinfunction "PB1_11") (pintype "bidirectional"))
    )
    (net (code "96") (name "/VIA_PB2") (class "Default")
      (node (ref "U4") (pin "11") (pinfunction "I/O11_11") (pintype "bidirectional"))
      (node (ref "U5") (pin "12") (pinfunction "PB2_12") (pintype "bidirectional"))
    )
    (net (code "97") (name "/VIA_PB3") (class "Default")
      (node (ref "U4") (pin "13") (pinfunction "I/O13_13") (pintype "bidirectional"))
      (node (ref "U5") (pin "13") (pinfunction "PB3_13") (pintype "bidirectional"))
    )
    (net (code "98") (name "/VIA_PB4") (class "Default")
      (node (ref "U4") (pin "15") (pinfunction "I/O15_15") (pintype "bidirectional"))
      (node (ref "U5") (pin "14") (pinfunction "PB4_14") (pintype "bidirectional"))
    )
    (net (code "99") (name "/VIA_PB5") (class "Default")
      (node (ref "U4") (pin "17") (pinfunction "I/O17_17") (pintype "bidirectional"))
      (node (ref "U5") (pin "15") (pinfunction "PB5_15") (pintype "bidirectional"))
    )
    (net (code "100") (name "/VIA_PB6") (class "Default")
      (node (ref "U4") (pin "19") (pinfunction "I/O19_19") (pintype "bidirectional"))
      (node (ref "U5") (pin "16") (pinfunction "PB6_16") (pintype "bidirectional"))
    )
    (net (code "101") (name "/VIA_PB7") (class "Default")
      (node (ref "U4") (pin "22") (pinfunction "I/O22/GCK1_22") (pintype "bidirectional"))
      (node (ref "U5") (pin "17") (pinfunction "PB7_17") (pintype "bidirectional"))
    )
    (net (code "102") (name "/modeSwitch") (class "Default")
      (node (ref "CN7") (pin "3") (pinfunction "3_3") (pintype "passive"))
      (node (ref "RN1") (pin "3") (pinfunction "3_3") (pintype "passive"))
      (node (ref "U4") (pin "70") (pinfunction "I/O70_70") (pintype "bidirectional"))
    )
    (net (code "103") (name "/~{CE}") (class "Default")
      (node (ref "CN2") (pin "18") (pinfunction "18_18") (pintype "passive"))
      (node (ref "U5") (pin "23") (pinfunction "~{CS2}_23") (pintype "input"))
    )
    (net (code "104") (name "/~{IRQ}") (class "Default")
      (node (ref "CN2") (pin "20") (pinfunction "20_20") (pintype "passive"))
      (node (ref "U5") (pin "21") (pinfunction "~{IRQ}_21") (pintype "open_collector"))
    )
    (net (code "105") (name "/~{RESET}") (class "Default")
      (node (ref "CN2") (pin "7") (pinfunction "7_7") (pintype "passive"))
      (node (ref "U4") (pin "25") (pinfunction "I/O25_25") (pintype "bidirectional"))
      (node (ref "U5") (pin "34") (pinfunction "~{RES}_34") (pintype "input"))
    )
    (net (code "106") (name "GND") (class "Default")
      (node (ref "C1") (pin "1") (pinfunction "1_1") (pintype "passive"))
      (node (ref "C10") (pin "1") (pinfunction "1_1") (pintype "passive"))
      (node (ref "C11") (pin "1") (pinfunction "1_1") (pintype "passive"))
      (node (ref "C12") (pin "1") (pinfunction "1_1") (pintype "passive"))
      (node (ref "C2") (pin "1") (pinfunction "1_1") (pintype "passive"))
      (node (ref "C3") (pin "1") (pinfunction "1_1") (pintype "passive"))
      (node (ref "C4") (pin "1") (pinfunction "1_1") (pintype "passive"))
      (node (ref "C5") (pin "1") (pinfunction "1_1") (pintype "passive"))
      (node (ref "C6") (pin "1") (pinfunction "1_1") (pintype "passive"))
      (node (ref "C7") (pin "1") (pinfunction "1_1") (pintype "passive"))
      (node (ref "C8") (pin "1") (pinfunction "1_1") (pintype "passive"))
      (node (ref "C9") (pin "1") (pinfunction "1_1") (pintype "passive"))
      (node (ref "CN1") (pin "1") (pinfunction "1_1") (pintype "passive"))
      (node (ref "CN4") (pin "12") (pinfunction "GND_12") (pintype "passive"))
      (node (ref "CN4") (pin "18") (pinfunction "GND_18") (pintype "passive"))
      (node (ref "CN4") (pin "19") (pinfunction "GND_19") (pintype "passive"))
      (node (ref "CN4") (pin "20") (pinfunction "GND_20") (pintype "passive"))
      (node (ref "CN4") (pin "21") (pinfunction "GND_21") (pintype "passive"))
      (node (ref "CN4") (pin "22") (pinfunction "GND_22") (pintype "passive"))
      (node (ref "CN4") (pin "23") (pinfunction "GND_23") (pintype "passive"))
      (node (ref "CN4") (pin "24") (pinfunction "GND_24") (pintype "passive"))
      (node (ref "CN5") (pin "3") (pinfunction "3_3") (pintype "passive"))
      (node (ref "CN6") (pin "6") (pinfunction "6_6") (pintype "passive"))
      (node (ref "CN7") (pin "2") (pinfunction "2_2") (pintype "passive"))
      (node (ref "CN7") (pin "4") (pinfunction "4_4") (pintype "passive"))
      (node (ref "CN7") (pin "6") (pinfunction "6_6") (pintype "passive"))
      (node (ref "CN7") (pin "8") (pinfunction "8_8") (pintype "passive"))
      (node (ref "D1") (pin "1") (pinfunction "1_1") (pintype "passive"))
      (node (ref "D2") (pin "1") (pinfunction "1_1") (pintype "passive"))
      (node (ref "D3") (pin "1") (pinfunction "1_1") (pintype "passive"))
      (node (ref "D4") (pin "1") (pinfunction "1_1") (pintype "passive"))
      (node (ref "Q1") (pin "2") (pinfunction "2_2") (pintype "passive"))
      (node (ref "Q2") (pin "2") (pinfunction "2_2") (pintype "passive"))
      (node (ref "U1") (pin "2") (pinfunction "GND_2") (pintype "power_in"))
      (node (ref "U2") (pin "10") (pinfunction "GND_10") (pintype "power_in"))
      (node (ref "U3") (pin "10") (pinfunction "GND_10") (pintype "power_in"))
      (node (ref "U4") (pin "100") (pinfunction "GND_100") (pintype "passive"))
      (node (ref "U4") (pin "21") (pinfunction "GND_21") (pintype "passive"))
      (node (ref "U4") (pin "31") (pinfunction "GND_31") (pintype "passive"))
      (node (ref "U4") (pin "44") (pinfunction "GND_44") (pintype "passive"))
      (node (ref "U4") (pin "62") (pinfunction "GND_62") (pintype "passive"))
      (node (ref "U4") (pin "69") (pinfunction "GND_69") (pintype "passive"))
      (node (ref "U4") (pin "75") (pinfunction "GND_75") (pintype "passive"))
      (node (ref "U4") (pin "84") (pinfunction "GND_84") (pintype "passive"))
      (node (ref "U5") (pin "1") (pinfunction "GND_1") (pintype "passive"))
    )
    (net (code "107") (name "Net-(D1-Pad2)") (class "Default")
      (node (ref "D1") (pin "2") (pinfunction "2_2") (pintype "passive"))
      (node (ref "R1") (pin "2") (pinfunction "2_2") (pintype "passive"))
    )
    (net (code "108") (name "Net-(D2-Pad2)") (class "Default")
      (node (ref "D2") (pin "2") (pinfunction "2_2") (pintype "passive"))
      (node (ref "R2") (pin "2") (pinfunction "2_2") (pintype "passive"))
    )
    (net (code "109") (name "Net-(D3-Pad2)") (class "Default")
      (node (ref "D3") (pin "2") (pinfunction "2_2") (pintype "passive"))
      (node (ref "R3") (pin "2") (pinfunction "2_2") (pintype "passive"))
    )
    (net (code "110") (name "Net-(D4-Pad2)") (class "Default")
      (node (ref "D4") (pin "2") (pinfunction "2_2") (pintype "passive"))
      (node (ref "R4") (pin "2") (pinfunction "2_2") (pintype "passive"))
    )
    (net (code "111") (name "unconnected-(CN1-Pad2)") (class "Default")
      (node (ref "CN1") (pin "2") (pinfunction "2_2") (pintype "passive+no_connect"))
    )
    (net (code "112") (name "unconnected-(CN1-Pad3)") (class "Default")
      (node (ref "CN1") (pin "3") (pinfunction "3_3") (pintype "passive+no_connect"))
    )
    (net (code "113") (name "unconnected-(CN1-Pad4)") (class "Default")
      (node (ref "CN1") (pin "4") (pinfunction "4_4") (pintype "passive+no_connect"))
    )
    (net (code "114") (name "unconnected-(CN1-Pad5)") (class "Default")
      (node (ref "CN1") (pin "5") (pinfunction "5_5") (pintype "passive+no_connect"))
    )
    (net (code "115") (name "unconnected-(CN1-Pad6)") (class "Default")
      (node (ref "CN1") (pin "6") (pinfunction "6_6") (pintype "passive+no_connect"))
    )
    (net (code "116") (name "unconnected-(CN1-Pad7)") (class "Default")
      (node (ref "CN1") (pin "7") (pinfunction "7_7") (pintype "passive+no_connect"))
    )
    (net (code "117") (name "unconnected-(CN1-Pad8)") (class "Default")
      (node (ref "CN1") (pin "8") (pinfunction "8_8") (pintype "passive+no_connect"))
    )
    (net (code "118") (name "unconnected-(CN1-Pad9)") (class "Default")
      (node (ref "CN1") (pin "9") (pinfunction "9_9") (pintype "passive+no_connect"))
    )
    (net (code "119") (name "unconnected-(CN1-Pad18)") (class "Default")
      (node (ref "CN1") (pin "18") (pinfunction "18_18") (pintype "passive+no_connect"))
    )
    (net (code "120") (name "unconnected-(CN1-Pad19)") (class "Default")
      (node (ref "CN1") (pin "19") (pinfunction "19_19") (pintype "passive+no_connect"))
    )
    (net (code "121") (name "unconnected-(CN2-Pad1)") (class "Default")
      (node (ref "CN2") (pin "1") (pinfunction "1_1") (pintype "passive+no_connect"))
    )
    (net (code "122") (name "unconnected-(CN2-Pad2)") (class "Default")
      (node (ref "CN2") (pin "2") (pinfunction "2_2") (pintype "passive+no_connect"))
    )
    (net (code "123") (name "unconnected-(U1-BYP-Pad4)") (class "Default")
      (node (ref "U1") (pin "4") (pinfunction "BYP_4") (pintype "passive+no_connect"))
    )
    (net (code "124") (name "unconnected-(U3-REN-Pad19)") (class "Default")
      (node (ref "U3") (pin "19") (pinfunction "REN_19") (pintype "bidirectional+no_connect"))
    )
    (net (code "125") (name "unconnected-(U3-SRQ-Pad12)") (class "Default")
      (node (ref "U3") (pin "12") (pinfunction "SRQ_12") (pintype "bidirectional+no_connect"))
    )
    (net (code "126") (name "unconnected-(U4-I{slash}O46-Pad46)") (class "Default")
      (node (ref "U4") (pin "46") (pinfunction "I/O46_46") (pintype "bidirectional"))
    )
    (net (code "127") (name "unconnected-(U4-I{slash}O50-Pad50)") (class "Default")
      (node (ref "U4") (pin "50") (pinfunction "I/O50_50") (pintype "bidirectional"))
    )
    (net (code "128") (name "unconnected-(U4-I{slash}O53-Pad53)") (class "Default")
      (node (ref "U4") (pin "53") (pinfunction "I/O53_53") (pintype "bidirectional"))
    )
    (net (code "129") (name "unconnected-(U4-I{slash}O54-Pad54)") (class "Default")
      (node (ref "U4") (pin "54") (pinfunction "I/O54_54") (pintype "bidirectional"))
    )
    (net (code "130") (name "unconnected-(U4-I{slash}O55-Pad55)") (class "Default")
      (node (ref "U4") (pin "55") (pinfunction "I/O55_55") (pintype "bidirectional"))
    )
    (net (code "131") (name "unconnected-(U4-I{slash}O56-Pad56)") (class "Default")
      (node (ref "U4") (pin "56") (pinfunction "I/O56_56") (pintype "bidirectional"))
    )
    (net (code "132") (name "unconnected-(U4-I{slash}O58-Pad58)") (class "Default")
      (node (ref "U4") (pin "58") (pinfunction "I/O58_58") (pintype "bidirectional"))
    )
    (net (code "133") (name "unconnected-(U4-I{slash}O59-Pad59)") (class "Default")
      (node (ref "U4") (pin "59") (pinfunction "I/O59_59") (pintype "bidirectional"))
    )
    (net (code "134") (name "unconnected-(U4-I{slash}O60-Pad60)") (class "Default")
      (node (ref "U4") (pin "60") (pinfunction "I/O60_60") (pintype "bidirectional"))
    )
    (net (code "135") (name "unconnected-(U4-I{slash}O61-Pad61)") (class "Default")
      (node (ref "U4") (pin "61") (pinfunction "I/O61_61") (pintype "bidirectional"))
    )
    (net (code "136") (name "unconnected-(U4-I{slash}O63-Pad63)") (class "Default")
      (node (ref "U4") (pin "63") (pinfunction "I/O63_63") (pintype "bidirectional"))
    )
    (net (code "137") (name "unconnected-(U4-I{slash}O64-Pad64)") (class "Default")
      (node (ref "U4") (pin "64") (pinfunction "I/O64_64") (pintype "bidirectional"))
    )
    (net (code "138") (name "unconnected-(U4-I{slash}O65-Pad65)") (class "Default")
      (node (ref "U4") (pin "65") (pinfunction "I/O65_65") (pintype "bidirectional"))
    )
    (net (code "139") (name "unconnected-(U4-I{slash}O66-Pad66)") (class "Default")
      (node (ref "U4") (pin "66") (pinfunction "I/O66_66") (pintype "bidirectional"))
    )
    (net (code "140") (name "unconnected-(U5-CB2-Pad19)") (class "Default")
      (node (ref "U5") (pin "19") (pinfunction "CB2_19") (pintype "bidirectional+no_connect"))
    )
  )
)
